# Memory.net
KiCad netlist of a schematic drawn in Altium Designer
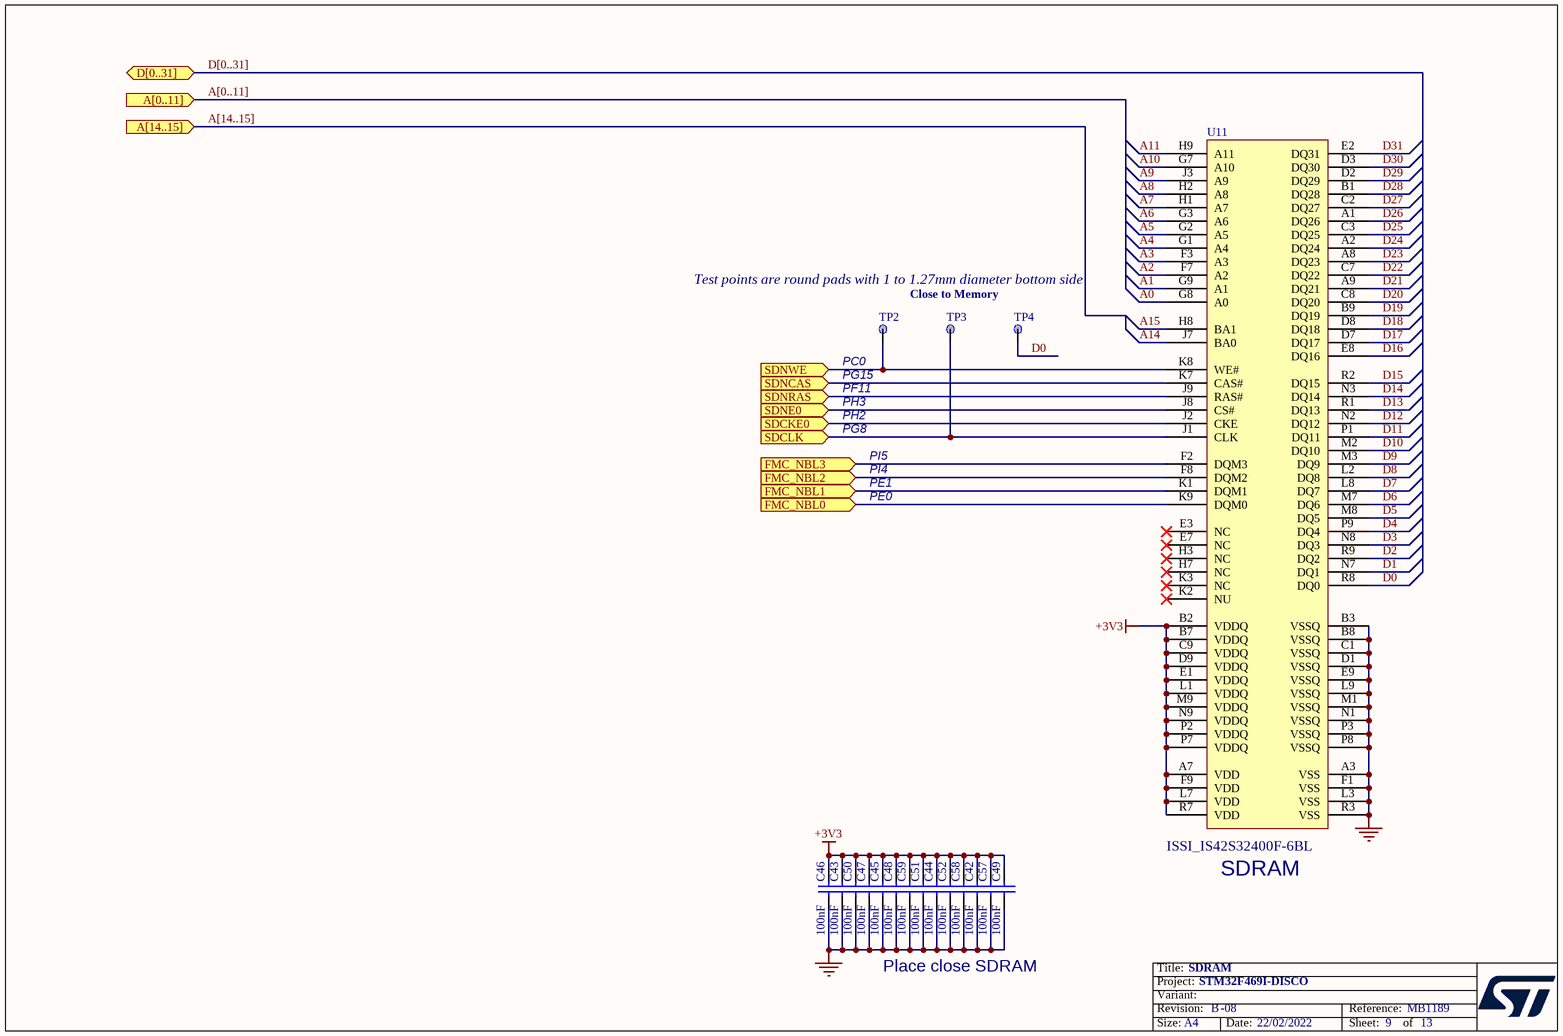
[diagram p0: Memory.SchDoc]

(export (version "E")
  (design (tool "Eeschema 10.0.6"))
  (components
    (comp (ref "C42")
      (value "100nF")
      (footprint "0402C")
      (description "Capacitor")
      (fields (field (name "PUBLISHER") "Altium Limited"))
      (libsource (lib "Miscellaneous Devices") (part "Cap"))
    )
    (comp (ref "C43")
      (value "100nF")
      (footprint "0402C")
      (description "Capacitor")
      (fields (field (name "PUBLISHER") "Altium Limited"))
      (libsource (lib "Miscellaneous Devices") (part "Cap"))
    )
    (comp (ref "C44")
      (value "100nF")
      (footprint "0402C")
      (description "Capacitor")
      (fields (field (name "PUBLISHER") "Altium Limited"))
      (libsource (lib "Miscellaneous Devices") (part "Cap"))
    )
    (comp (ref "C45")
      (value "100nF")
      (footprint "0402C")
      (description "Capacitor")
      (fields (field (name "PUBLISHER") "Altium Limited"))
      (libsource (lib "Miscellaneous Devices") (part "Cap"))
    )
    (comp (ref "C46")
      (value "100nF")
      (footprint "0402C")
      (description "Capacitor")
      (fields (field (name "PUBLISHER") "Altium Limited"))
      (libsource (lib "Miscellaneous Devices") (part "Cap"))
    )
    (comp (ref "C47")
      (value "100nF")
      (footprint "0402C")
      (description "Capacitor")
      (fields (field (name "PUBLISHER") "Altium Limited"))
      (libsource (lib "Miscellaneous Devices") (part "Cap"))
    )
    (comp (ref "C48")
      (value "100nF")
      (footprint "0402C")
      (description "Capacitor")
      (fields (field (name "PUBLISHER") "Altium Limited"))
      (libsource (lib "Miscellaneous Devices") (part "Cap"))
    )
    (comp (ref "C49")
      (value "100nF")
      (footprint "0402C")
      (description "Capacitor")
      (fields (field (name "PUBLISHER") "Altium Limited"))
      (libsource (lib "Miscellaneous Devices") (part "Cap"))
    )
    (comp (ref "C50")
      (value "100nF")
      (footprint "0402C")
      (description "Capacitor")
      (fields (field (name "PUBLISHER") "Altium Limited"))
      (libsource (lib "Miscellaneous Devices") (part "Cap"))
    )
    (comp (ref "C51")
      (value "100nF")
      (footprint "0402C")
      (description "Capacitor")
      (fields (field (name "PUBLISHER") "Altium Limited"))
      (libsource (lib "Miscellaneous Devices") (part "Cap"))
    )
    (comp (ref "C52")
      (value "100nF")
      (footprint "0402C")
      (description "Capacitor")
      (fields (field (name "PUBLISHER") "Altium Limited"))
      (libsource (lib "Miscellaneous Devices") (part "Cap"))
    )
    (comp (ref "C57")
      (value "100nF")
      (footprint "0402C")
      (description "Capacitor")
      (fields (field (name "PUBLISHER") "Altium Limited"))
      (libsource (lib "Miscellaneous Devices") (part "Cap"))
    )
    (comp (ref "C58")
      (value "100nF")
      (footprint "0402C")
      (description "Capacitor")
      (fields (field (name "PUBLISHER") "Altium Limited"))
      (libsource (lib "Miscellaneous Devices") (part "Cap"))
    )
    (comp (ref "C59")
      (value "100nF")
      (footprint "0402C")
      (description "Capacitor")
      (fields (field (name "PUBLISHER") "Altium Limited"))
      (libsource (lib "Miscellaneous Devices") (part "Cap"))
    )
    (comp (ref "TP2") (value "TP") (footprint "TP_C40") (libsource (lib "Almos") (part "TP")))
    (comp (ref "TP3") (value "TP") (footprint "TP_C40") (libsource (lib "Almos") (part "TP")))
    (comp (ref "TP4") (value "TP") (footprint "TP_C40") (libsource (lib "Almos") (part "TP")))
    (comp (ref "U11")
      (value "ISSI_IS42S32400F-6BL")
      (footprint "FBGA90_0R8_8X13")
      (libsource (lib "mb1045") (part "MT48LC4M32B2B5"))
    )
  )
  (nets
    (net (code "1") (name "+3V3") (class "Default")
      (node (ref "C42") (pin "1") (pinfunction "1_1") (pintype "passive"))
      (node (ref "C43") (pin "1") (pinfunction "1_1") (pintype "passive"))
      (node (ref "C44") (pin "1") (pinfunction "1_1") (pintype "passive"))
      (node (ref "C45") (pin "1") (pinfunction "1_1") (pintype "passive"))
      (node (ref "C46") (pin "1") (pinfunction "1_1") (pintype "passive"))
      (node (ref "C47") (pin "1") (pinfunction "1_1") (pintype "passive"))
      (node (ref "C48") (pin "1") (pinfunction "1_1") (pintype "passive"))
      (node (ref "C49") (pin "1") (pinfunction "1_1") (pintype "passive"))
      (node (ref "C50") (pin "1") (pinfunction "1_1") (pintype "passive"))
      (node (ref "C51") (pin "1") (pinfunction "1_1") (pintype "passive"))
      (node (ref "C52") (pin "1") (pinfunction "1_1") (pintype "passive"))
      (node (ref "C57") (pin "1") (pinfunction "1_1") (pintype "passive"))
      (node (ref "C58") (pin "1") (pinfunction "1_1") (pintype "passive"))
      (node (ref "C59") (pin "1") (pinfunction "1_1") (pintype "passive"))
      (node (ref "U11") (pin "A7") (pinfunction "VDD_A7") (pintype "passive"))
      (node (ref "U11") (pin "B2") (pinfunction "VDDQ_B2") (pintype "passive"))
      (node (ref "U11") (pin "B7") (pinfunction "VDDQ_B7") (pintype "passive"))
      (node (ref "U11") (pin "C9") (pinfunction "VDDQ_C9") (pintype "passive"))
      (node (ref "U11") (pin "D9") (pinfunction "VDDQ_D9") (pintype "passive"))
      (node (ref "U11") (pin "E1") (pinfunction "VDDQ_E1") (pintype "passive"))
      (node (ref "U11") (pin "F9") (pinfunction "VDD_F9") (pintype "passive"))
      (node (ref "U11") (pin "L1") (pinfunction "VDDQ_L1") (pintype "passive"))
      (node (ref "U11") (pin "L7") (pinfunction "VDD_L7") (pintype "passive"))
      (node (ref "U11") (pin "M9") (pinfunction "VDDQ_M9") (pintype "passive"))
      (node (ref "U11") (pin "N9") (pinfunction "VDDQ_N9") (pintype "passive"))
      (node (ref "U11") (pin "P2") (pinfunction "VDDQ_P2") (pintype "passive"))
      (node (ref "U11") (pin "P7") (pinfunction "VDDQ_P7") (pintype "passive"))
      (node (ref "U11") (pin "R7") (pinfunction "VDD_R7") (pintype "passive"))
    )
    (net (code "2") (name "/A0") (class "Default")
      (node (ref "U11") (pin "G8") (pinfunction "A0_G8") (pintype "passive"))
    )
    (net (code "3") (name "/A1") (class "Default")
      (node (ref "U11") (pin "G9") (pinfunction "A1_G9") (pintype "passive"))
    )
    (net (code "4") (name "/A2") (class "Default")
      (node (ref "U11") (pin "F7") (pinfunction "A2_F7") (pintype "passive"))
    )
    (net (code "5") (name "/A3") (class "Default")
      (node (ref "U11") (pin "F3") (pinfunction "A3_F3") (pintype "passive"))
    )
    (net (code "6") (name "/A4") (class "Default")
      (node (ref "U11") (pin "G1") (pinfunction "A4_G1") (pintype "passive"))
    )
    (net (code "7") (name "/A5") (class "Default")
      (node (ref "U11") (pin "G2") (pinfunction "A5_G2") (pintype "passive"))
    )
    (net (code "8") (name "/A6") (class "Default")
      (node (ref "U11") (pin "G3") (pinfunction "A6_G3") (pintype "passive"))
    )
    (net (code "9") (name "/A7") (class "Default")
      (node (ref "U11") (pin "H1") (pinfunction "A7_H1") (pintype "passive"))
    )
    (net (code "10") (name "/A8") (class "Default")
      (node (ref "U11") (pin "H2") (pinfunction "A8_H2") (pintype "passive"))
    )
    (net (code "11") (name "/A9") (class "Default")
      (node (ref "U11") (pin "J3") (pinfunction "A9_J3") (pintype "passive"))
    )
    (net (code "12") (name "/A10") (class "Default")
      (node (ref "U11") (pin "G7") (pinfunction "A10_G7") (pintype "passive"))
    )
    (net (code "13") (name "/A11") (class "Default")
      (node (ref "U11") (pin "H9") (pinfunction "A11_H9") (pintype "passive"))
    )
    (net (code "14") (name "/A14") (class "Default")
      (node (ref "U11") (pin "J7") (pinfunction "BA0_J7") (pintype "passive"))
    )
    (net (code "15") (name "/A15") (class "Default")
      (node (ref "U11") (pin "H8") (pinfunction "BA1_H8") (pintype "passive"))
    )
    (net (code "18") (name "/D0") (class "Default")
      (node (ref "TP4") (pin "1") (pinfunction "1_1") (pintype "passive"))
      (node (ref "U11") (pin "R8") (pinfunction "DQ0_R8") (pintype "passive"))
    )
    (net (code "19") (name "/D1") (class "Default")
      (node (ref "U11") (pin "N7") (pinfunction "DQ1_N7") (pintype "passive"))
    )
    (net (code "20") (name "/D2") (class "Default")
      (node (ref "U11") (pin "R9") (pinfunction "DQ2_R9") (pintype "passive"))
    )
    (net (code "21") (name "/D3") (class "Default")
      (node (ref "U11") (pin "N8") (pinfunction "DQ3_N8") (pintype "passive"))
    )
    (net (code "22") (name "/D4") (class "Default")
      (node (ref "U11") (pin "P9") (pinfunction "DQ4_P9") (pintype "passive"))
    )
    (net (code "23") (name "/D5") (class "Default")
      (node (ref "U11") (pin "M8") (pinfunction "DQ5_M8") (pintype "passive"))
    )
    (net (code "24") (name "/D6") (class "Default")
      (node (ref "U11") (pin "M7") (pinfunction "DQ6_M7") (pintype "passive"))
    )
    (net (code "25") (name "/D7") (class "Default")
      (node (ref "U11") (pin "L8") (pinfunction "DQ7_L8") (pintype "passive"))
    )
    (net (code "26") (name "/D8") (class "Default")
      (node (ref "U11") (pin "L2") (pinfunction "DQ8_L2") (pintype "passive"))
    )
    (net (code "27") (name "/D9") (class "Default")
      (node (ref "U11") (pin "M3") (pinfunction "DQ9_M3") (pintype "passive"))
    )
    (net (code "28") (name "/D10") (class "Default")
      (node (ref "U11") (pin "M2") (pinfunction "DQ10_M2") (pintype "passive"))
    )
    (net (code "29") (name "/D11") (class "Default")
      (node (ref "U11") (pin "P1") (pinfunction "DQ11_P1") (pintype "passive"))
    )
    (net (code "30") (name "/D12") (class "Default")
      (node (ref "U11") (pin "N2") (pinfunction "DQ12_N2") (pintype "passive"))
    )
    (net (code "31") (name "/D13") (class "Default")
      (node (ref "U11") (pin "R1") (pinfunction "DQ13_R1") (pintype "passive"))
    )
    (net (code "32") (name "/D14") (class "Default")
      (node (ref "U11") (pin "N3") (pinfunction "DQ14_N3") (pintype "passive"))
    )
    (net (code "33") (name "/D15") (class "Default")
      (node (ref "U11") (pin "R2") (pinfunction "DQ15_R2") (pintype "passive"))
    )
    (net (code "34") (name "/D16") (class "Default")
      (node (ref "U11") (pin "E8") (pinfunction "DQ16_E8") (pintype "passive"))
    )
    (net (code "35") (name "/D17") (class "Default")
      (node (ref "U11") (pin "D7") (pinfunction "DQ17_D7") (pintype "passive"))
    )
    (net (code "36") (name "/D18") (class "Default")
      (node (ref "U11") (pin "D8") (pinfunction "DQ18_D8") (pintype "passive"))
    )
    (net (code "37") (name "/D19") (class "Default")
      (node (ref "U11") (pin "B9") (pinfunction "DQ19_B9") (pintype "passive"))
    )
    (net (code "38") (name "/D20") (class "Default")
      (node (ref "U11") (pin "C8") (pinfunction "DQ20_C8") (pintype "passive"))
    )
    (net (code "39") (name "/D21") (class "Default")
      (node (ref "U11") (pin "A9") (pinfunction "DQ21_A9") (pintype "passive"))
    )
    (net (code "40") (name "/D22") (class "Default")
      (node (ref "U11") (pin "C7") (pinfunction "DQ22_C7") (pintype "passive"))
    )
    (net (code "41") (name "/D23") (class "Default")
      (node (ref "U11") (pin "A8") (pinfunction "DQ23_A8") (pintype "passive"))
    )
    (net (code "42") (name "/D24") (class "Default")
      (node (ref "U11") (pin "A2") (pinfunction "DQ24_A2") (pintype "passive"))
    )
    (net (code "43") (name "/D25") (class "Default")
      (node (ref "U11") (pin "C3") (pinfunction "DQ25_C3") (pintype "passive"))
    )
    (net (code "44") (name "/D26") (class "Default")
      (node (ref "U11") (pin "A1") (pinfunction "DQ26_A1") (pintype "passive"))
    )
    (net (code "45") (name "/D27") (class "Default")
      (node (ref "U11") (pin "C2") (pinfunction "DQ27_C2") (pintype "passive"))
    )
    (net (code "46") (name "/D28") (class "Default")
      (node (ref "U11") (pin "B1") (pinfunction "DQ28_B1") (pintype "passive"))
    )
    (net (code "47") (name "/D29") (class "Default")
      (node (ref "U11") (pin "D2") (pinfunction "DQ29_D2") (pintype "passive"))
    )
    (net (code "48") (name "/D30") (class "Default")
      (node (ref "U11") (pin "D3") (pinfunction "DQ30_D3") (pintype "passive"))
    )
    (net (code "49") (name "/D31") (class "Default")
      (node (ref "U11") (pin "E2") (pinfunction "DQ31_E2") (pintype "passive"))
    )
    (net (code "51") (name "/FMC_NBL0") (class "Default")
      (node (ref "U11") (pin "K9") (pinfunction "DQM0_K9") (pintype "passive"))
    )
    (net (code "52") (name "/FMC_NBL1") (class "Default")
      (node (ref "U11") (pin "K1") (pinfunction "DQM1_K1") (pintype "passive"))
    )
    (net (code "53") (name "/FMC_NBL2") (class "Default")
      (node (ref "U11") (pin "F8") (pinfunction "DQM2_F8") (pintype "passive"))
    )
    (net (code "54") (name "/FMC_NBL3") (class "Default")
      (node (ref "U11") (pin "F2") (pinfunction "DQM3_F2") (pintype "passive"))
    )
    (net (code "55") (name "/SDCKE0") (class "Default")
      (node (ref "U11") (pin "J2") (pinfunction "CKE_J2") (pintype "passive"))
    )
    (net (code "56") (name "/SDCLK") (class "Default")
      (node (ref "TP3") (pin "1") (pinfunction "1_1") (pintype "passive"))
      (node (ref "U11") (pin "J1") (pinfunction "CLK_J1") (pintype "passive"))
    )
    (net (code "57") (name "/SDNCAS") (class "Default")
      (node (ref "U11") (pin "K7") (pinfunction "CAS#_K7") (pintype "passive"))
    )
    (net (code "58") (name "/SDNE0") (class "Default")
      (node (ref "U11") (pin "J8") (pinfunction "CS#_J8") (pintype "passive"))
    )
    (net (code "59") (name "/SDNRAS") (class "Default")
      (node (ref "U11") (pin "J9") (pinfunction "RAS#_J9") (pintype "passive"))
    )
    (net (code "60") (name "/SDNWE") (class "Default")
      (node (ref "TP2") (pin "1") (pinfunction "1_1") (pintype "passive"))
      (node (ref "U11") (pin "K8") (pinfunction "WE#_K8") (pintype "passive"))
    )
    (net (code "61") (name "GND") (class "Default")
      (node (ref "C42") (pin "2") (pinfunction "2_2") (pintype "passive"))
      (node (ref "C43") (pin "2") (pinfunction "2_2") (pintype "passive"))
      (node (ref "C44") (pin "2") (pinfunction "2_2") (pintype "passive"))
      (node (ref "C45") (pin "2") (pinfunction "2_2") (pintype "passive"))
      (node (ref "C46") (pin "2") (pinfunction "2_2") (pintype "passive"))
      (node (ref "C47") (pin "2") (pinfunction "2_2") (pintype "passive"))
      (node (ref "C48") (pin "2") (pinfunction "2_2") (pintype "passive"))
      (node (ref "C49") (pin "2") (pinfunction "2_2") (pintype "passive"))
      (node (ref "C50") (pin "2") (pinfunction "2_2") (pintype "passive"))
      (node (ref "C51") (pin "2") (pinfunction "2_2") (pintype "passive"))
      (node (ref "C52") (pin "2") (pinfunction "2_2") (pintype "passive"))
      (node (ref "C57") (pin "2") (pinfunction "2_2") (pintype "passive"))
      (node (ref "C58") (pin "2") (pinfunction "2_2") (pintype "passive"))
      (node (ref "C59") (pin "2") (pinfunction "2_2") (pintype "passive"))
      (node (ref "U11") (pin "A3") (pinfunction "VSS_A3") (pintype "passive"))
      (node (ref "U11") (pin "B3") (pinfunction "VSSQ_B3") (pintype "passive"))
      (node (ref "U11") (pin "B8") (pinfunction "VSSQ_B8") (pintype "passive"))
      (node (ref "U11") (pin "C1") (pinfunction "VSSQ_C1") (pintype "passive"))
      (node (ref "U11") (pin "D1") (pinfunction "VSSQ_D1") (pintype "passive"))
      (node (ref "U11") (pin "E9") (pinfunction "VSSQ_E9") (pintype "passive"))
      (node (ref "U11") (pin "F1") (pinfunction "VSS_F1") (pintype "passive"))
      (node (ref "U11") (pin "L3") (pinfunction "VSS_L3") (pintype "passive"))
      (node (ref "U11") (pin "L9") (pinfunction "VSSQ_L9") (pintype "passive"))
      (node (ref "U11") (pin "M1") (pinfunction "VSSQ_M1") (pintype "passive"))
      (node (ref "U11") (pin "N1") (pinfunction "VSSQ_N1") (pintype "passive"))
      (node (ref "U11") (pin "P3") (pinfunction "VSSQ_P3") (pintype "passive"))
      (node (ref "U11") (pin "P8") (pinfunction "VSSQ_P8") (pintype "passive"))
      (node (ref "U11") (pin "R3") (pinfunction "VSS_R3") (pintype "passive"))
    )
    (net (code "62") (name "unconnected-(U11-NC-PadE3)") (class "Default")
      (node (ref "U11") (pin "E3") (pinfunction "NC_E3") (pintype "passive+no_connect"))
    )
    (net (code "63") (name "unconnected-(U11-NC-PadE7)") (class "Default")
      (node (ref "U11") (pin "E7") (pinfunction "NC_E7") (pintype "passive+no_connect"))
    )
    (net (code "64") (name "unconnected-(U11-NC-PadH3)") (class "Default")
      (node (ref "U11") (pin "H3") (pinfunction "NC_H3") (pintype "passive+no_connect"))
    )
    (net (code "65") (name "unconnected-(U11-NC-PadH7)") (class "Default")
      (node (ref "U11") (pin "H7") (pinfunction "NC_H7") (pintype "passive+no_connect"))
    )
    (net (code "66") (name "unconnected-(U11-NC-PadK3)") (class "Default")
      (node (ref "U11") (pin "K3") (pinfunction "NC_K3") (pintype "passive+no_connect"))
    )
    (net (code "67") (name "unconnected-(U11-NU-PadK2)") (class "Default")
      (node (ref "U11") (pin "K2") (pinfunction "NU_K2") (pintype "passive+no_connect"))
    )
  )
)
